# STMod.net
KiCad netlist of a schematic drawn in Altium Designer
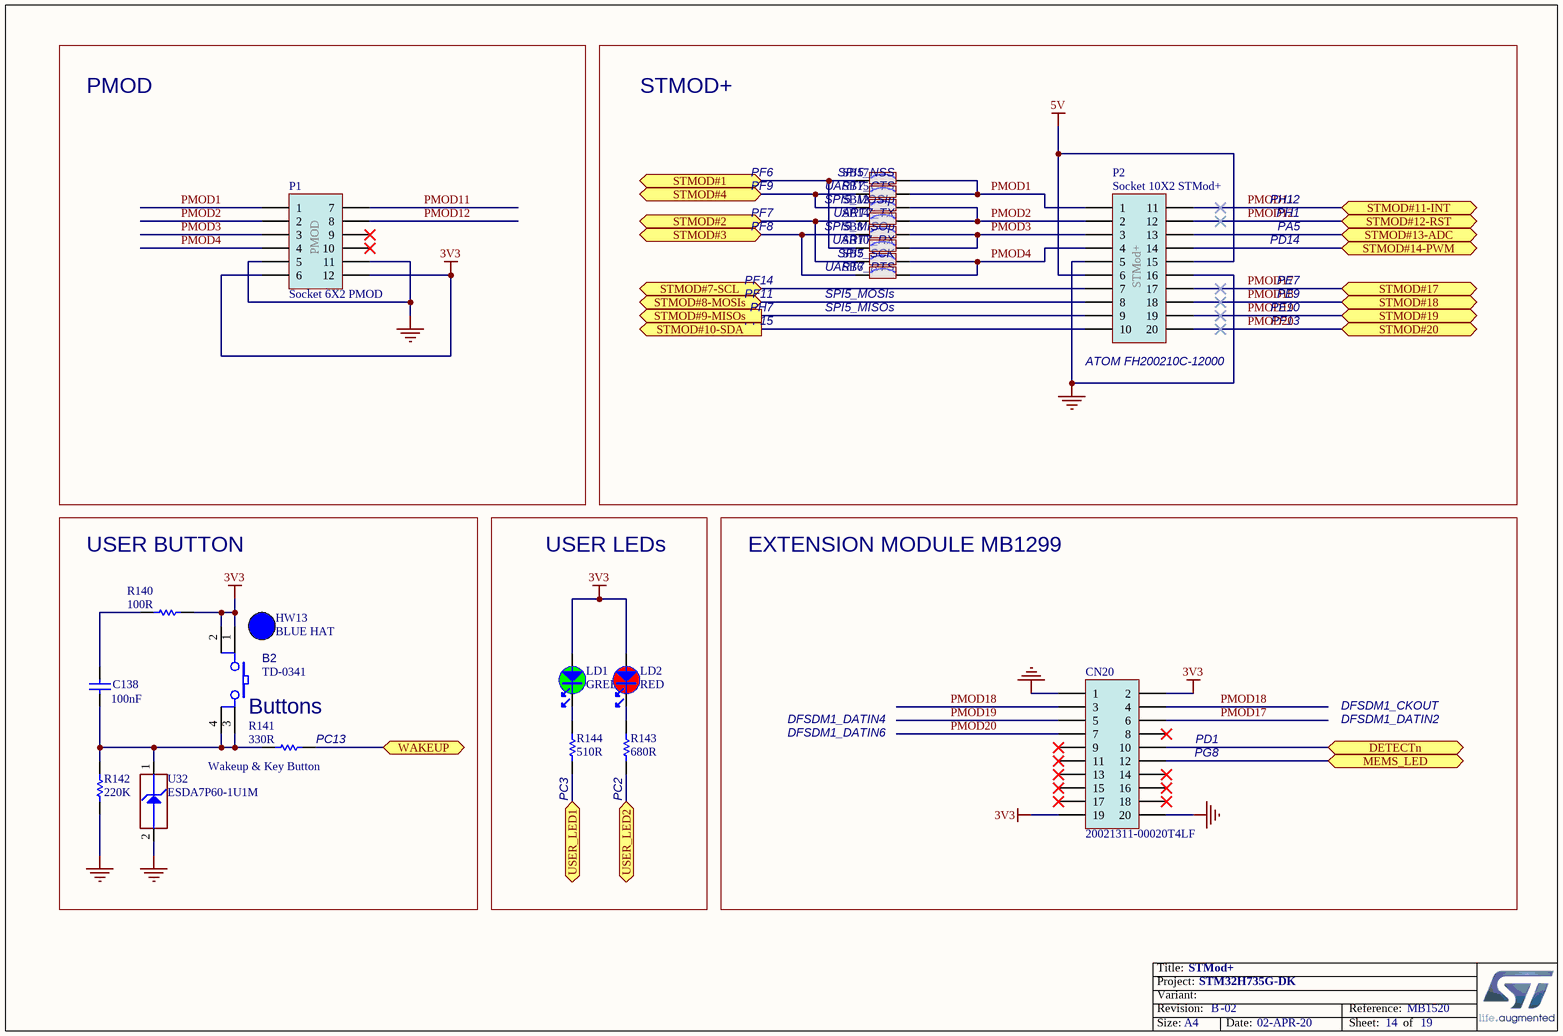
[diagram p0: STMod+.SchDoc]

(export (version "E")
  (design (tool "Eeschema 10.0.6"))
  (components
    (comp (ref "B2")
      (value "SW-PUSH-CMS")
      (footprint "SWI_WEALTHMETAL_TD-0341_4P_BLUE")
      (description "Non-Open Push-Button 0.1A 24V")
      (fields
        (field (name "INTERNAL_PART_NUMBER") "MCD-00002")
        (field (name "MANUFACTURER_PART_NUMBER") "TD-0341")
        (field (name "MANUFACTURER") "WEALTHMETAL")
        (field (name "PROVIDED_BY") "SUBCO")
      )
      (libsource (lib "MCD_PARTS_database") (part "SW-PUSH-CMS"))
    )
    (comp (ref "C138")
      (value "100nF")
      (footprint "C0402")
      (description "Capacitor, MLCC, 100nF, 16V, X7R, 10%, 0402, T=0,5mm")
      (fields
        (field (name "INTERNAL_PART_NUMBER") "MCD-00102")
        (field (name "MANUFACTURER_PART_NUMBER") "CC0402KRX7R7BB104")
        (field (name "PROVIDED_BY") "SUBCO")
      )
      (libsource (lib "MCD_PARTS_database") (part "Capacitor"))
    )
    (comp (ref "CN20")
      (value "20021311-00020T4LF")
      (footprint "CON_FCI_20021311-XXX20XXLF")
      (description "Socket for MB1299, 10x2, 1.27mm, VR, TH, Height 4.30mm/2.40mm")
      (fields
        (field (name "INTERNAL_PART_NUMBER") "MCD-00147")
        (field (name "MANUFACTURER") "FCI")
        (field (name "PROVIDED_BY") "SUBCO")
      )
      (libsource (lib "MCD_PARTS_database") (part "Socket 10x2"))
    )
    (comp (ref "HW13")
      (value "BLUE HAT")
      (description "Blue Hat for switch TD0341X-G01-BLU")
      (fields
        (field (name "INTERNAL_PART_NUMBER") "MCD-00634")
        (field (name "MANUFACTURER_PART_NUMBER") "988.16.09.3.00002_SH-517")
        (field (name "PROVIDED_BY") "SUBCO")
      )
      (libsource (lib "MCD_PARTS_database") (part "BUTTON_HAT_BLUE"))
    )
    (comp (ref "LD1")
      (value "GREEN")
      (footprint "LED_0603_GREEN")
      (description "LED, Green, 0603")
      (fields
        (field (name "INTERNAL_PART_NUMBER") "MCD-00050")
        (field (name "MANUFACTURER_PART_NUMBER") "19-213SYGC/S530-E2/TR8")
        (field (name "PROVIDED_BY") "SUBCO")
      )
      (libsource (lib "MCD_PARTS_database") (part "LED_green"))
    )
    (comp (ref "LD2")
      (value "RED")
      (footprint "LED_0603_RED")
      (description "LED, Red, 0603")
      (fields
        (field (name "INTERNAL_PART_NUMBER") "MCD-00049")
        (field (name "MANUFACTURER_PART_NUMBER") "19-213-R6C-AP1Q2B/3T")
        (field (name "PROVIDED_BY") "SUBCO")
      )
      (libsource (lib "MCD_PARTS_database") (part "LED_red"))
    )
    (comp (ref "P1")
      (value "Socket 6X2 PMOD")
      (footprint "CON_SAMTEC_SSW-106-02-F-D-RA__PMOD")
      (description "Socket, 6x2, 2.54mm, TH, RA, Height 8.51mm/7.62mm")
      (fields
        (field (name "INTERNAL_PART_NUMBER") "MCD-00308")
        (field (name "MANUFACTURER_PART_NUMBER") "SSW-106-02-F-D-RA")
        (field (name "PROVIDED_BY") "SUBCO")
      )
      (libsource (lib "MCD_PARTS_database") (part "Socket 6X2 PMOD"))
    )
    (comp (ref "P2")
      (value "Socket 10X2 STMod+")
      (footprint "CON_SAMTEC_SQT-110-01-F-D-RA__STMOD+")
      (description "Socket 10x2, 2.00mm, RA, TH, Height 6.35mm/2.29mm")
      (fields
        (field (name "INTERNAL_PART_NUMBER") "MCD-00309")
        (field (name "MANUFACTURER_PART_NUMBER") "SQT-110-01-F-D-RA")
        (field (name "PROVIDED_BY") "SUBCO")
      )
      (libsource (lib "MCD_PARTS_database") (part "Socket 10X2 STMod+"))
    )
    (comp (ref "R140")
      (value "100R")
      (footprint "R0402")
      (description "Resistor,100R,0402,1%,1/16W")
      (fields
        (field (name "INTERNAL_PART_NUMBER") "MCD-00119")
        (field (name "MANUFACTURER_PART_NUMBER") "RC0402FR-07100RL")
        (field (name "PROVIDED_BY") "SUBCO")
      )
      (libsource (lib "MCD_PARTS_database") (part "Resistor"))
    )
    (comp (ref "R141")
      (value "330R")
      (footprint "R0402")
      (description "Resistor,330R,0402,1%,1/16W")
      (fields
        (field (name "INTERNAL_PART_NUMBER") "MCD-00062")
        (field (name "MANUFACTURER_PART_NUMBER") "RC0402FR-07330RL")
        (field (name "PROVIDED_BY") "SUBCO")
      )
      (libsource (lib "MCD_PARTS_database") (part "Resistor"))
    )
    (comp (ref "R142")
      (value "220K")
      (footprint "R0402")
      (description "Resistor,220K,0402,1%,1/16W")
      (fields
        (field (name "INTERNAL_PART_NUMBER") "MCD-00164")
        (field (name "MANUFACTURER_PART_NUMBER") "RC0402FR-07220KL")
        (field (name "PROVIDED_BY") "SUBCO")
      )
      (libsource (lib "MCD_PARTS_database") (part "Resistor"))
    )
    (comp (ref "R143")
      (value "680R")
      (footprint "R0603")
      (description "Resistor,680R,0603,1%,1/10W")
      (fields
        (field (name "INTERNAL_PART_NUMBER") "MCD-00508")
        (field (name "MANUFACTURER_PART_NUMBER") "RC0603FR-07680RL")
        (field (name "PROVIDED_BY") "SUBCO")
      )
      (libsource (lib "MCD_PARTS_database") (part "Resistor"))
    )
    (comp (ref "R144")
      (value "510R")
      (footprint "R0603")
      (description "Resistor,510R,0603,1%,1/10W")
      (fields
        (field (name "INTERNAL_PART_NUMBER") "MCD-00225")
        (field (name "MANUFACTURER_PART_NUMBER") "RC0603FR-07510RL")
        (field (name "PROVIDED_BY") "SUBCO")
      )
      (libsource (lib "MCD_PARTS_database") (part "Resistor"))
    )
    (comp (ref "SB6")
      (value "SB_ON")
      (footprint "SOLDER-BRIDGE_R0603-0R")
      (description "Solder Bridge ON")
      (fields
        (field (name "INTERNAL_PART_NUMBER") "MCD-00071")
        (field (name "MANUFACTURER_PART_NUMBER") "RC0603JR-070RL")
        (field (name "PROVIDED_BY") "SUBCO")
      )
      (libsource (lib "MCD_PARTS_database") (part "SB_ON"))
    )
    (comp (ref "SB7")
      (value "SB_ON")
      (footprint "SOLDER-BRIDGE_R0603-0R")
      (description "Solder Bridge ON")
      (fields
        (field (name "INTERNAL_PART_NUMBER") "MCD-00071")
        (field (name "MANUFACTURER_PART_NUMBER") "RC0603JR-070RL")
        (field (name "PROVIDED_BY") "SUBCO")
      )
      (libsource (lib "MCD_PARTS_database") (part "SB_ON"))
    )
    (comp (ref "SB8")
      (value "SB_ON")
      (footprint "SOLDER-BRIDGE_R0603-0R")
      (description "Solder Bridge ON")
      (fields
        (field (name "INTERNAL_PART_NUMBER") "MCD-00071")
        (field (name "MANUFACTURER_PART_NUMBER") "RC0603JR-070RL")
        (field (name "PROVIDED_BY") "SUBCO")
      )
      (libsource (lib "MCD_PARTS_database") (part "SB_ON"))
    )
    (comp (ref "SB10")
      (value "SB_ON")
      (footprint "SOLDER-BRIDGE_R0603-0R")
      (description "Solder Bridge ON")
      (fields
        (field (name "INTERNAL_PART_NUMBER") "MCD-00071")
        (field (name "MANUFACTURER_PART_NUMBER") "RC0603JR-070RL")
        (field (name "PROVIDED_BY") "SUBCO")
      )
      (libsource (lib "MCD_PARTS_database") (part "SB_ON"))
    )
    (comp (ref "SB12")
      (value "SB_ON")
      (footprint "SOLDER-BRIDGE_R0603-0R")
      (description "Solder Bridge ON")
      (fields
        (field (name "INTERNAL_PART_NUMBER") "MCD-00071")
        (field (name "MANUFACTURER_PART_NUMBER") "RC0603JR-070RL")
        (field (name "PROVIDED_BY") "SUBCO")
      )
      (libsource (lib "MCD_PARTS_database") (part "SB_ON"))
    )
    (comp (ref "SB14")
      (value "SB_ON")
      (footprint "SOLDER-BRIDGE_R0603-0R")
      (description "Solder Bridge ON")
      (fields
        (field (name "INTERNAL_PART_NUMBER") "MCD-00071")
        (field (name "MANUFACTURER_PART_NUMBER") "RC0603JR-070RL")
        (field (name "PROVIDED_BY") "SUBCO")
      )
      (libsource (lib "MCD_PARTS_database") (part "SB_ON"))
    )
    (comp (ref "SB15")
      (value "SB_ON")
      (footprint "SOLDER-BRIDGE_R0603-0R")
      (description "Solder Bridge ON")
      (fields
        (field (name "INTERNAL_PART_NUMBER") "MCD-00071")
        (field (name "MANUFACTURER_PART_NUMBER") "RC0603JR-070RL")
        (field (name "PROVIDED_BY") "SUBCO")
      )
      (libsource (lib "MCD_PARTS_database") (part "SB_ON"))
    )
    (comp (ref "SB17")
      (value "SB_ON")
      (footprint "SOLDER-BRIDGE_R0603-0R")
      (description "Solder Bridge ON")
      (fields
        (field (name "INTERNAL_PART_NUMBER") "MCD-00071")
        (field (name "MANUFACTURER_PART_NUMBER") "RC0603JR-070RL")
        (field (name "PROVIDED_BY") "SUBCO")
      )
      (libsource (lib "MCD_PARTS_database") (part "SB_ON"))
    )
    (comp (ref "U32")
      (value "ESDA7P60-1U1M")
      (footprint "ESD_QFN2_1P6X1_P125")
      (description "High power transient voltage suppressor, 7V breakdown")
      (fields
        (field (name "INTERNAL_PART_NUMBER") "MCD-00251")
        (field (name "MANUFACTURER") "STMICROELECTRONICS")
        (field (name "PROVIDED_BY") "SUBCO with ST control")
      )
      (libsource (lib "MCD_PARTS_database") (part "ESD-TRANSIL"))
    )
  )
  (nets
    (net (code "1") (name "/DETECTn") (class "Default")
      (node (ref "CN20") (pin "10") (pinfunction "10_10") (pintype "passive"))
    )
    (net (code "2") (name "/MEMS_LED") (class "Default")
      (node (ref "CN20") (pin "12") (pinfunction "12_12") (pintype "passive"))
    )
    (net (code "3") (name "/PMOD1") (class "Default")
      (node (ref "P1") (pin "1") (pinfunction "1_1") (pintype "passive"))
      (node (ref "P2") (pin "1") (pinfunction "1_1") (pintype "passive"))
      (node (ref "SB15") (pin "2") (pinfunction "2_2") (pintype "passive"))
      (node (ref "SB17") (pin "2") (pinfunction "2_2") (pintype "passive"))
    )
    (net (code "4") (name "/PMOD2") (class "Default")
      (node (ref "P1") (pin "2") (pinfunction "2_2") (pintype "passive"))
      (node (ref "P2") (pin "2") (pinfunction "2_2") (pintype "passive"))
      (node (ref "SB12") (pin "2") (pinfunction "2_2") (pintype "passive"))
      (node (ref "SB14") (pin "2") (pinfunction "2_2") (pintype "passive"))
    )
    (net (code "5") (name "/PMOD3") (class "Default")
      (node (ref "P1") (pin "3") (pinfunction "3_3") (pintype "passive"))
      (node (ref "P2") (pin "3") (pinfunction "3_3") (pintype "passive"))
      (node (ref "SB10") (pin "2") (pinfunction "2_2") (pintype "passive"))
      (node (ref "SB8") (pin "2") (pinfunction "2_2") (pintype "passive"))
    )
    (net (code "6") (name "/PMOD4") (class "Default")
      (node (ref "P1") (pin "4") (pinfunction "4_4") (pintype "passive"))
      (node (ref "P2") (pin "4") (pinfunction "4_4") (pintype "passive"))
      (node (ref "SB6") (pin "2") (pinfunction "2_2") (pintype "passive"))
      (node (ref "SB7") (pin "2") (pinfunction "2_2") (pintype "passive"))
    )
    (net (code "7") (name "/PMOD11") (class "Default")
      (node (ref "P1") (pin "7") (pinfunction "7_7") (pintype "passive"))
      (node (ref "P2") (pin "11") (pinfunction "11_11") (pintype "passive"))
    )
    (net (code "8") (name "/PMOD12") (class "Default")
      (node (ref "P1") (pin "8") (pinfunction "8_8") (pintype "passive"))
      (node (ref "P2") (pin "12") (pinfunction "12_12") (pintype "passive"))
    )
    (net (code "9") (name "/PMOD17") (class "Default")
      (node (ref "CN20") (pin "6") (pinfunction "6_6") (pintype "passive"))
      (node (ref "P2") (pin "17") (pinfunction "17_17") (pintype "passive"))
    )
    (net (code "10") (name "/PMOD18") (class "Default")
      (node (ref "CN20") (pin "3") (pinfunction "3_3") (pintype "passive"))
      (node (ref "CN20") (pin "4") (pinfunction "4_4") (pintype "passive"))
      (node (ref "P2") (pin "18") (pinfunction "18_18") (pintype "passive"))
    )
    (net (code "11") (name "/PMOD19") (class "Default")
      (node (ref "CN20") (pin "5") (pinfunction "5_5") (pintype "passive"))
      (node (ref "P2") (pin "19") (pinfunction "19_19") (pintype "passive"))
    )
    (net (code "12") (name "/PMOD20") (class "Default")
      (node (ref "CN20") (pin "7") (pinfunction "7_7") (pintype "passive"))
      (node (ref "P2") (pin "20") (pinfunction "20_20") (pintype "passive"))
    )
    (net (code "13") (name "/STMOD#1") (class "Default")
      (node (ref "SB10") (pin "1") (pinfunction "1_1") (pintype "passive"))
      (node (ref "SB17") (pin "1") (pinfunction "1_1") (pintype "passive"))
    )
    (net (code "14") (name "/STMOD#2") (class "Default")
      (node (ref "SB14") (pin "1") (pinfunction "1_1") (pintype "passive"))
      (node (ref "SB7") (pin "1") (pinfunction "1_1") (pintype "passive"))
    )
    (net (code "15") (name "/STMOD#3") (class "Default")
      (node (ref "SB6") (pin "1") (pinfunction "1_1") (pintype "passive"))
      (node (ref "SB8") (pin "1") (pinfunction "1_1") (pintype "passive"))
    )
    (net (code "16") (name "/STMOD#4") (class "Default")
      (node (ref "SB12") (pin "1") (pinfunction "1_1") (pintype "passive"))
      (node (ref "SB15") (pin "1") (pinfunction "1_1") (pintype "passive"))
    )
    (net (code "17") (name "/STMOD#7-SCL") (class "Default")
      (node (ref "P2") (pin "7") (pinfunction "7_7") (pintype "passive"))
    )
    (net (code "18") (name "/STMOD#8-MOSIs") (class "Default")
      (node (ref "P2") (pin "8") (pinfunction "8_8") (pintype "passive"))
    )
    (net (code "19") (name "/STMOD#9-MISOs") (class "Default")
      (node (ref "P2") (pin "9") (pinfunction "9_9") (pintype "passive"))
    )
    (net (code "20") (name "/STMOD#10-SDA") (class "Default")
      (node (ref "P2") (pin "10") (pinfunction "10_10") (pintype "passive"))
    )
    (net (code "21") (name "/STMOD#13-ADC") (class "Default")
      (node (ref "P2") (pin "13") (pinfunction "13_13") (pintype "passive"))
    )
    (net (code "22") (name "/STMOD#14-PWM") (class "Default")
      (node (ref "P2") (pin "14") (pinfunction "14_14") (pintype "passive"))
    )
    (net (code "23") (name "/USER_LED1") (class "Default")
      (node (ref "R144") (pin "1") (pinfunction "1_1") (pintype "passive"))
    )
    (net (code "24") (name "/USER_LED2") (class "Default")
      (node (ref "R143") (pin "1") (pinfunction "1_1") (pintype "passive"))
    )
    (net (code "25") (name "/WAKEUP") (class "Default")
      (node (ref "R141") (pin "2") (pinfunction "2_2") (pintype "passive"))
    )
    (net (code "26") (name "3V3") (class "Default")
      (node (ref "B2") (pin "1") (pinfunction "1_1") (pintype "passive"))
      (node (ref "B2") (pin "2") (pinfunction "2_2") (pintype "passive"))
      (node (ref "CN20") (pin "19") (pinfunction "19_19") (pintype "passive"))
      (node (ref "CN20") (pin "2") (pinfunction "2_2") (pintype "passive"))
      (node (ref "LD1") (pin "1") (pintype "passive"))
      (node (ref "LD2") (pin "1") (pintype "passive"))
      (node (ref "P1") (pin "12") (pinfunction "12_12") (pintype "passive"))
      (node (ref "P1") (pin "6") (pinfunction "6_6") (pintype "passive"))
      (node (ref "R140") (pin "2") (pinfunction "2_2") (pintype "passive"))
    )
    (net (code "27") (name "5V") (class "Default")
      (node (ref "P2") (pin "15") (pinfunction "15_15") (pintype "passive"))
      (node (ref "P2") (pin "6") (pinfunction "6_6") (pintype "passive"))
    )
    (net (code "28") (name "GND") (class "Default")
      (node (ref "CN20") (pin "1") (pinfunction "1_1") (pintype "passive"))
      (node (ref "CN20") (pin "20") (pinfunction "20_20") (pintype "passive"))
      (node (ref "P1") (pin "11") (pinfunction "11_11") (pintype "passive"))
      (node (ref "P1") (pin "5") (pinfunction "5_5") (pintype "passive"))
      (node (ref "P2") (pin "16") (pinfunction "16_16") (pintype "passive"))
      (node (ref "P2") (pin "5") (pinfunction "5_5") (pintype "passive"))
      (node (ref "R142") (pin "1") (pinfunction "1_1") (pintype "passive"))
      (node (ref "U32") (pin "2") (pinfunction "GND_2") (pintype "passive"))
    )
    (net (code "29") (name "Net-(C138-Pad1)") (class "Default")
      (node (ref "C138") (pin "1") (pinfunction "1_1") (pintype "passive"))
      (node (ref "R140") (pin "1") (pinfunction "1_1") (pintype "passive"))
    )
    (net (code "30") (name "Net-(LD1-Pad2)") (class "Default")
      (node (ref "LD1") (pin "2") (pintype "passive"))
      (node (ref "R144") (pin "2") (pinfunction "2_2") (pintype "passive"))
    )
    (net (code "31") (name "Net-(LD2-Pad2)") (class "Default")
      (node (ref "LD2") (pin "2") (pintype "passive"))
      (node (ref "R143") (pin "2") (pinfunction "2_2") (pintype "passive"))
    )
    (net (code "32") (name "Net-(U32-IO1)") (class "Default")
      (node (ref "B2") (pin "3") (pinfunction "3_3") (pintype "passive"))
      (node (ref "B2") (pin "4") (pinfunction "4_4") (pintype "passive"))
      (node (ref "C138") (pin "2") (pinfunction "2_2") (pintype "passive"))
      (node (ref "R141") (pin "1") (pinfunction "1_1") (pintype "passive"))
      (node (ref "R142") (pin "2") (pinfunction "2_2") (pintype "passive"))
      (node (ref "U32") (pin "1") (pinfunction "IO1_1") (pintype "passive"))
    )
    (net (code "33") (name "unconnected-(CN20-Pad8)") (class "Default")
      (node (ref "CN20") (pin "8") (pinfunction "8_8") (pintype "passive+no_connect"))
    )
    (net (code "34") (name "unconnected-(CN20-Pad9)") (class "Default")
      (node (ref "CN20") (pin "9") (pinfunction "9_9") (pintype "passive+no_connect"))
    )
    (net (code "35") (name "unconnected-(CN20-Pad11)") (class "Default")
      (node (ref "CN20") (pin "11") (pinfunction "11_11") (pintype "passive+no_connect"))
    )
    (net (code "36") (name "unconnected-(CN20-Pad13)") (class "Default")
      (node (ref "CN20") (pin "13") (pinfunction "13_13") (pintype "passive+no_connect"))
    )
    (net (code "37") (name "unconnected-(CN20-Pad14)") (class "Default")
      (node (ref "CN20") (pin "14") (pinfunction "14_14") (pintype "passive+no_connect"))
    )
    (net (code "38") (name "unconnected-(CN20-Pad15)") (class "Default")
      (node (ref "CN20") (pin "15") (pinfunction "15_15") (pintype "passive+no_connect"))
    )
    (net (code "39") (name "unconnected-(CN20-Pad16)") (class "Default")
      (node (ref "CN20") (pin "16") (pinfunction "16_16") (pintype "passive+no_connect"))
    )
    (net (code "40") (name "unconnected-(CN20-Pad17)") (class "Default")
      (node (ref "CN20") (pin "17") (pinfunction "17_17") (pintype "passive+no_connect"))
    )
    (net (code "41") (name "unconnected-(CN20-Pad18)") (class "Default")
      (node (ref "CN20") (pin "18") (pinfunction "18_18") (pintype "passive+no_connect"))
    )
    (net (code "42") (name "unconnected-(P1-Pad9)") (class "Default")
      (node (ref "P1") (pin "9") (pinfunction "9_9") (pintype "passive+no_connect"))
    )
    (net (code "43") (name "unconnected-(P1-Pad10)") (class "Default")
      (node (ref "P1") (pin "10") (pinfunction "10_10") (pintype "passive+no_connect"))
    )
  )
)
